# TUDSSL_condenar__Hardware_PCBs_Misc_Ligh.net
KiCad netlist of a schematic drawn in Altium Designer
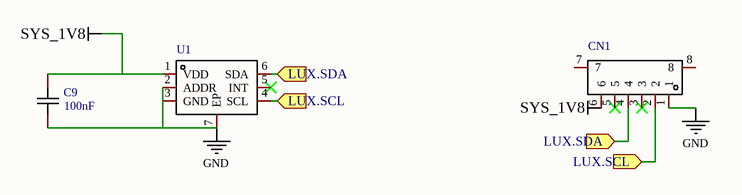
[diagram p0: TUDSSL_condenar__Hardware_PCBs_Misc_LightSensingModule_Schematic3__1_P1.schdoc]

(export (version "E")
  (design (tool "Eeschema 10.0.6"))
  (components
    (comp (ref "C9")
      (value "100nF")
      (fields
        (field (name "NAME") "100nF")
        (field (name "MANUFACTURER") "YAGEO")
        (field (name "MANUFACTURER PART") "CC0603KRX7R9BB104")
      )
      (libsource (lib "altium-import") (part "root_3_CC0603KRX7R9BB104_"))
    )
    (comp (ref "CN1")
      (value "532610671")
      (fields (field (name "MANUFACTURER") "MOLEX"))
      (libsource (lib "altium-import") (part "root_1_mirrored_532610671_"))
    )
    (comp (ref "U1")
      (value "OPT3001DNPR")
      (fields (field (name "MANUFACTURER") "TI(德州仪器)"))
      (libsource (lib "altium-import") (part "root_0_OPT3001DNPR_"))
    )
  )
  (nets
    (net (code "1") (name "/LUX.SCL") (class "Default")
      (node (ref "CN1") (pin "2") (pinfunction "2_2") (pintype "passive"))
      (node (ref "U1") (pin "4") (pinfunction "SCL_4") (pintype "passive"))
    )
    (net (code "2") (name "/LUX.SDA") (class "Default")
      (node (ref "CN1") (pin "4") (pinfunction "4_4") (pintype "passive"))
      (node (ref "U1") (pin "6") (pinfunction "SDA_6") (pintype "passive"))
    )
    (net (code "3") (name "GND") (class "Default")
      (node (ref "C9") (pin "2") (pinfunction "2_2") (pintype "passive"))
      (node (ref "CN1") (pin "1") (pinfunction "1_1") (pintype "passive"))
      (node (ref "U1") (pin "2") (pinfunction "ADDR_2") (pintype "passive"))
      (node (ref "U1") (pin "3") (pinfunction "GND_3") (pintype "passive"))
      (node (ref "U1") (pin "7") (pinfunction "EP_7") (pintype "passive"))
    )
    (net (code "4") (name "SYS_1V8") (class "Default")
      (node (ref "C9") (pin "1") (pinfunction "1_1") (pintype "passive"))
      (node (ref "CN1") (pin "6") (pinfunction "6_6") (pintype "passive"))
      (node (ref "U1") (pin "1") (pinfunction "VDD_1") (pintype "passive"))
    )
    (net (code "5") (name "unconnected-(CN1-Pad3)") (class "Default")
      (node (ref "CN1") (pin "3") (pinfunction "3_3") (pintype "passive+no_connect"))
    )
    (net (code "6") (name "unconnected-(CN1-Pad5)") (class "Default")
      (node (ref "CN1") (pin "5") (pinfunction "5_5") (pintype "passive+no_connect"))
    )
    (net (code "7") (name "unconnected-(CN1-Pad7)") (class "Default")
      (node (ref "CN1") (pin "7") (pinfunction "7_7") (pintype "passive"))
    )
    (net (code "8") (name "unconnected-(CN1-Pad8)") (class "Default")
      (node (ref "CN1") (pin "8") (pinfunction "8_8") (pintype "passive"))
    )
    (net (code "9") (name "unconnected-(U1-INT-Pad5)") (class "Default")
      (node (ref "U1") (pin "5") (pinfunction "INT_5") (pintype "passive+no_connect"))
    )
  )
)
